# Amplifier_Section.net
KiCad netlist of a schematic drawn in Altium Designer
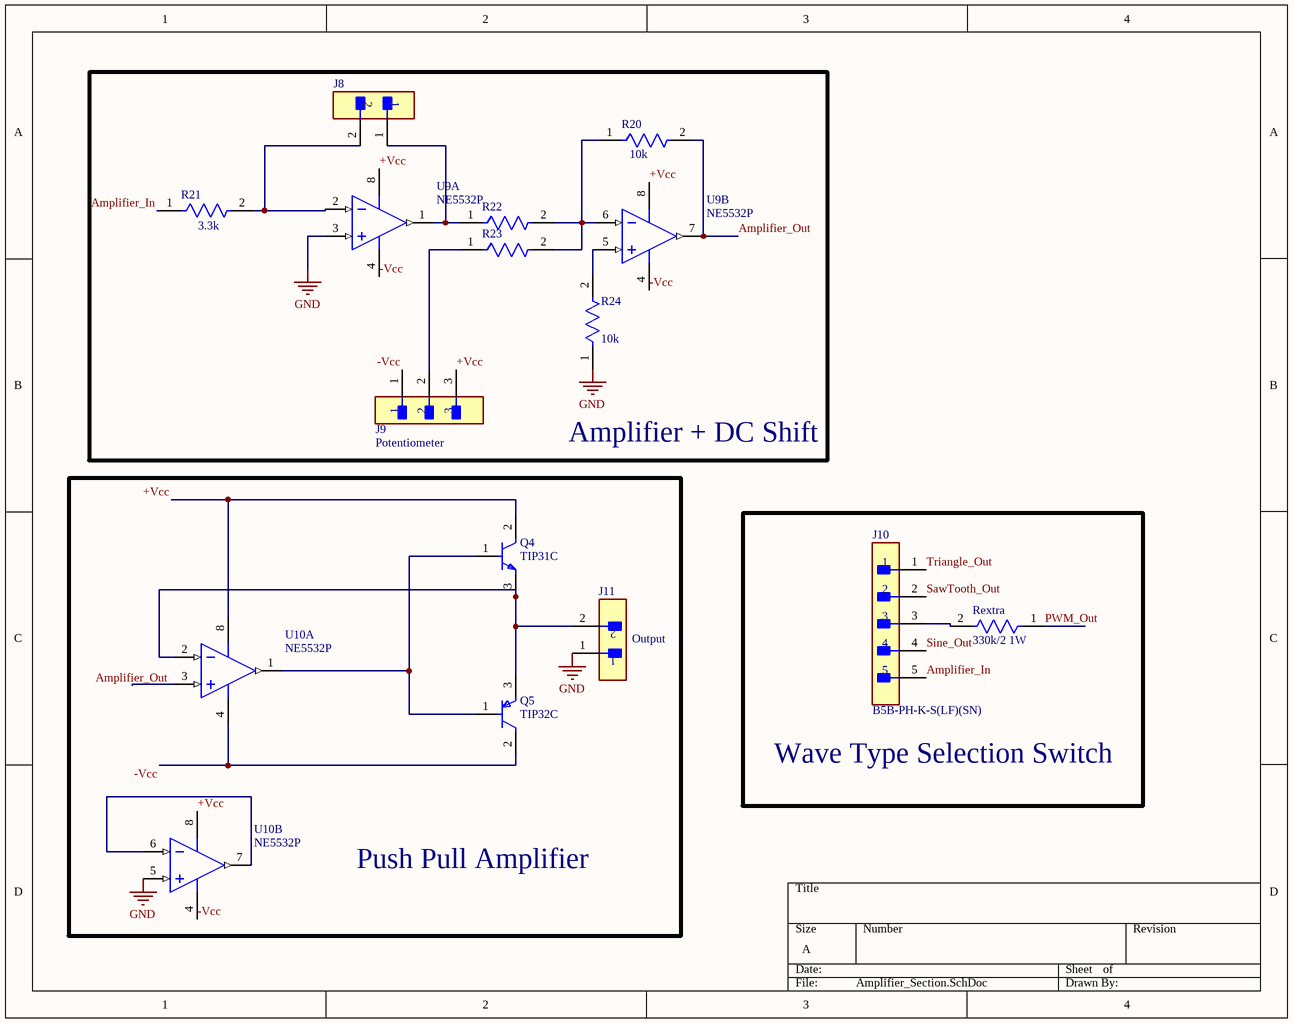
[diagram p0: Amplifier_Section.SchDoc]

(export (version "E")
  (design (tool "Eeschema 10.0.6"))
  (components
    (comp (ref "J8")
      (value "~")
      (footprint "FP-B2B-XH-A_LF_SN-MFG")
      (description "CONN HEADER VERT 2POS 2.5MM")
      (libsource (lib "Altium Content Vault") (part "3bc925449376181038e59eaffc5286c"))
    )
    (comp (ref "J9")
      (value "Potentiometer")
      (footprint "FP-440054-3-MFG")
      (description "CONN HEADER VERT 3POS 2MM")
      (fields
        (field (name "OCTOPART") "https://octopart.com/440054-3-te+connectivity-40394845")
        (field (name "MANUFACTURER") "TE Connectivity")
      )
      (libsource (lib "Altium Content Vault") (part "0d3f023dd272f625e17a2be33dea85f"))
    )
    (comp (ref "J10")
      (value "B5B-PH-K-S(LF)(SN)")
      (footprint "FP-B5B-PH-K-S_LF_SN-MFG")
      (description "CONN HEADER VERT 5POS 2MM")
      (libsource (lib "Altium Content Vault") (part "bf93c07fd2649a848d0ec8585582aab"))
    )
    (comp (ref "J11")
      (value "Output")
      (footprint "FP-B2B-XH-A_LF_SN-MFG")
      (description "CONN HEADER VERT 2POS 2.5MM")
      (libsource (lib "") (part "3bc925449376181038e59eaffc5286c_1"))
    )
    (comp (ref "Q4")
      (value "TIP31C")
      (footprint "FP-TO-220-P0A0015988-MFG")
      (description "TRANS NPN 100V 3A TO-220")
      (fields
        (field (name "OCTOPART") "https://octopart.com/tip31c-stmicroelectronics-15555")
        (field (name "MANUFACTURER") "STMicroelectronics")
      )
      (libsource (lib "Altium Content Vault") (part "1c57d9dae74fe2702546667b0e849db"))
    )
    (comp (ref "Q5")
      (value "TIP32C")
      (footprint "FP-TO-220-P0A0015988-MFG")
      (description "TRANS PNP 100V 3A TO-220")
      (fields
        (field (name "MANUFACTURER") "STMicroelectronics")
        (field (name "OCTOPART") "https://octopart.com/tip32c-stmicroelectronics-353617")
      )
      (libsource (lib "Altium Content Vault") (part "802a31d42ca070764d097f06bc9597f"))
    )
    (comp (ref "R20")
      (value "10k")
      (footprint "FP-VR37-MFG")
      (description "RES 1.2M OHM 5% 1/2W AXIAL")
      (fields (field (name "TOLERANCE") "5%"))
      (libsource (lib "Altium Content Vault") (part "1029c3af85768c4190bb7ad29bc67b5"))
    )
    (comp (ref "R21")
      (value "3.3k")
      (footprint "FP-VR37-MFG")
      (description "RES 1.2M OHM 5% 1/2W AXIAL")
      (fields (field (name "TOLERANCE") "5%"))
      (libsource (lib "Altium Content Vault") (part "1029c3af85768c4190bb7ad29bc67b5"))
    )
    (comp (ref "R22")
      (value "~")
      (footprint "FP-VR37-MFG")
      (description "RES 1.2M OHM 5% 1/2W AXIAL")
      (fields (field (name "TOLERANCE") "5%"))
      (libsource (lib "Altium Content Vault") (part "1029c3af85768c4190bb7ad29bc67b5"))
    )
    (comp (ref "R23")
      (value "~")
      (footprint "FP-VR37-MFG")
      (description "RES 1.2M OHM 5% 1/2W AXIAL")
      (fields (field (name "TOLERANCE") "5%"))
      (libsource (lib "Altium Content Vault") (part "1029c3af85768c4190bb7ad29bc67b5"))
    )
    (comp (ref "R24")
      (value "10k")
      (footprint "FP-VR37-MFG")
      (description "RES 1.2M OHM 5% 1/2W AXIAL")
      (fields (field (name "TOLERANCE") "5%"))
      (libsource (lib "Altium Content Vault") (part "1029c3af85768c4190bb7ad29bc67b5"))
    )
    (comp (ref "Rextra")
      (value "330k/2 1W")
      (footprint "FP-RR01-MFG")
      (description "RES 100K OHM 5% 1W AXIAL")
      (fields (field (name "TOLERANCE") "5%"))
      (libsource (lib "Altium Content Vault") (part "1029c3af85768c4190bb7ad29bc67b5"))
    )
    (comp (ref "U9")
      (value "NE5532P")
      (footprint "P0008A")
      (fields (field (name "MANUFACTURER") "Texas Instruments"))
      (libsource (lib "Altium Content Vault") (part "TI-AMP-D6-2-8_D"))
    )
    (comp (ref "U10")
      (value "NE5532P")
      (footprint "P0008A")
      (fields (field (name "MANUFACTURER") "Texas Instruments"))
      (libsource (lib "Altium Content Vault") (part "TI-AMP-D6-2-8_D"))
    )
  )
  (nets
    (net (code "1") (name "/+Vcc") (class "Default")
      (node (ref "J9") (pin "3") (pinfunction "3_3") (pintype "passive"))
      (node (ref "Q4") (pin "2") (pinfunction "C_2") (pintype "passive"))
      (node (ref "U10") (pin "8") (pinfunction "VCC+_8") (pintype "power_in"))
      (node (ref "U9") (pin "8") (pinfunction "VCC+_8") (pintype "power_in"))
    )
    (net (code "2") (name "/-Vcc") (class "Default")
      (node (ref "J9") (pin "1") (pinfunction "1_1") (pintype "passive"))
      (node (ref "Q5") (pin "2") (pinfunction "C_2") (pintype "passive"))
      (node (ref "U10") (pin "4") (pinfunction "VCC-_4") (pintype "power_in"))
      (node (ref "U9") (pin "4") (pinfunction "VCC-_4") (pintype "power_in"))
    )
    (net (code "3") (name "/Amplifier_In") (class "Default")
      (node (ref "J10") (pin "5") (pinfunction "5_5") (pintype "passive"))
      (node (ref "R21") (pin "1") (pinfunction "1_1") (pintype "passive"))
    )
    (net (code "4") (name "/Amplifier_Out") (class "Default")
      (node (ref "R20") (pin "2") (pinfunction "2_2") (pintype "passive"))
      (node (ref "U10") (pin "3") (pinfunction "IN1+_3") (pintype "input"))
      (node (ref "U9") (pin "7") (pinfunction "OUT2_7") (pintype "output"))
    )
    (net (code "5") (name "/PWM_Out") (class "Default")
      (node (ref "Rextra") (pin "1") (pinfunction "1_1") (pintype "passive"))
    )
    (net (code "6") (name "/SawTooth_Out") (class "Default")
      (node (ref "J10") (pin "2") (pinfunction "2_2") (pintype "passive"))
    )
    (net (code "7") (name "/Sine_Out") (class "Default")
      (node (ref "J10") (pin "4") (pinfunction "4_4") (pintype "passive"))
    )
    (net (code "8") (name "/Triangle_Out") (class "Default")
      (node (ref "J10") (pin "1") (pinfunction "1_1") (pintype "passive"))
    )
    (net (code "9") (name "GND") (class "Default")
      (node (ref "J11") (pin "1") (pinfunction "1_1") (pintype "passive"))
      (node (ref "R24") (pin "1") (pinfunction "1_1") (pintype "passive"))
      (node (ref "U10") (pin "5") (pinfunction "IN2+_5") (pintype "input"))
      (node (ref "U9") (pin "3") (pinfunction "IN1+_3") (pintype "input"))
    )
    (net (code "10") (name "Net-(J9-Pad2)") (class "Default")
      (node (ref "J9") (pin "2") (pinfunction "2_2") (pintype "passive"))
      (node (ref "R23") (pin "1") (pinfunction "1_1") (pintype "passive"))
    )
    (net (code "11") (name "Net-(J10-Pad3)") (class "Default")
      (node (ref "J10") (pin "3") (pinfunction "3_3") (pintype "passive"))
      (node (ref "Rextra") (pin "2") (pinfunction "2_2") (pintype "passive"))
    )
    (net (code "12") (name "Net-(Q4-B)") (class "Default")
      (node (ref "Q4") (pin "1") (pinfunction "B_1") (pintype "passive"))
      (node (ref "Q5") (pin "1") (pinfunction "B_1") (pintype "passive"))
      (node (ref "U10") (pin "1") (pinfunction "OUT1_1") (pintype "output"))
    )
    (net (code "13") (name "Net-(Q4-E)") (class "Default")
      (node (ref "J11") (pin "2") (pinfunction "2_2") (pintype "passive"))
      (node (ref "Q4") (pin "3") (pinfunction "E_3") (pintype "passive"))
      (node (ref "Q5") (pin "3") (pinfunction "E_3") (pintype "passive"))
      (node (ref "U10") (pin "2") (pinfunction "IN1-_2") (pintype "input"))
    )
    (net (code "14") (name "Net-(U9A-IN1-)") (class "Default")
      (node (ref "J8") (pin "2") (pinfunction "2_2") (pintype "passive"))
      (node (ref "R21") (pin "2") (pinfunction "2_2") (pintype "passive"))
      (node (ref "U9") (pin "2") (pinfunction "IN1-_2") (pintype "input"))
    )
    (net (code "15") (name "Net-(U9A-OUT1)") (class "Default")
      (node (ref "J8") (pin "1") (pinfunction "1_1") (pintype "passive"))
      (node (ref "R22") (pin "1") (pinfunction "1_1") (pintype "passive"))
      (node (ref "U9") (pin "1") (pinfunction "OUT1_1") (pintype "output"))
    )
    (net (code "16") (name "Net-(U9B-IN2+)") (class "Default")
      (node (ref "R24") (pin "2") (pinfunction "2_2") (pintype "passive"))
      (node (ref "U9") (pin "5") (pinfunction "IN2+_5") (pintype "input"))
    )
    (net (code "17") (name "Net-(U9B-IN2-)") (class "Default")
      (node (ref "R20") (pin "1") (pinfunction "1_1") (pintype "passive"))
      (node (ref "R22") (pin "2") (pinfunction "2_2") (pintype "passive"))
      (node (ref "R23") (pin "2") (pinfunction "2_2") (pintype "passive"))
      (node (ref "U9") (pin "6") (pinfunction "IN2-_6") (pintype "input"))
    )
    (net (code "18") (name "Net-(U10B-IN2-)") (class "Default")
      (node (ref "U10") (pin "6") (pinfunction "IN2-_6") (pintype "input"))
      (node (ref "U10") (pin "7") (pinfunction "OUT2_7") (pintype "output"))
    )
  )
)
